# blinky_board.net
KiCad netlist of a schematic drawn in EAGLE
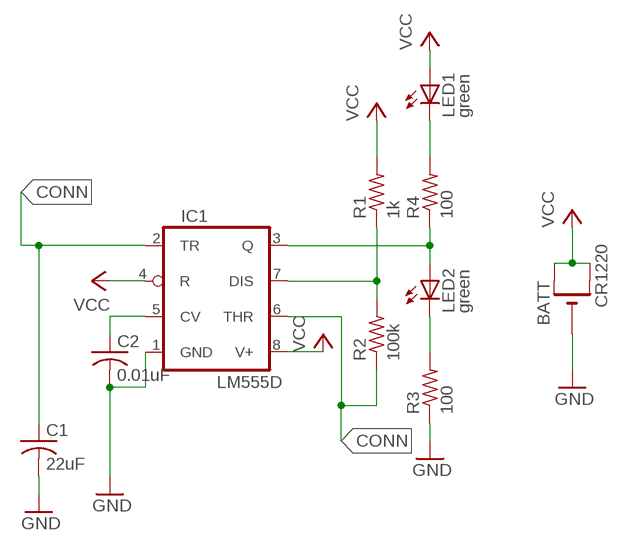
[diagram p0: schematic, sheet 1]

(export (version "E")
  (design (tool "Eeschema 10.0.6"))
  (components
    (comp (ref "BATT")
      (value "CR1220")
      (footprint "eagle-import:CR1220-SMD")
      (libsource (lib "eagle-import") (part "CR1220SMT"))
    )
    (comp (ref "C1")
      (value "22uF")
      (footprint "eagle-import:C0805")
      (fields (field (name "MF") "SAMSUNG ELECTRO-MECHANICS") (field (name "MPN") "CL21A226MPCLRNC"))
      (libsource (lib "eagle-import") (part "C-USC0805"))
    )
    (comp (ref "C2")
      (value "0.01uF")
      (footprint "eagle-import:C0805")
      (fields (field (name "MF") "KEMET") (field (name "MPN") "C0805J103K3RACAUTO"))
      (libsource (lib "eagle-import") (part "C-USC0805"))
    )
    (comp (ref "IC1")
      (value "LM555D")
      (footprint "eagle-import:SO08")
      (fields (field (name "MF") "TEXAS INSTRUMENTS") (field (name "MPN") "TLC555CDR"))
      (libsource (lib "eagle-import") (part "555DLM"))
    )
    (comp (ref "LED1")
      (value "green")
      (footprint "eagle-import:CHIPLED_0805")
      (fields (field (name "MF") "LUMEX") (field (name "MPN") "SML-LX0805GC-TR"))
      (libsource (lib "eagle-import") (part "LEDCHIPLED_0805"))
    )
    (comp (ref "LED2")
      (value "green")
      (footprint "eagle-import:CHIPLED_0805")
      (fields (field (name "MF") "LUMEX") (field (name "MPN") "SML-LX0805GC-TR"))
      (libsource (lib "eagle-import") (part "LEDCHIPLED_0805"))
    )
    (comp (ref "R1")
      (value "1k")
      (footprint "eagle-import:R0805")
      (fields (field (name "MF") "PANASONIC") (field (name "MPN") "EXBN8V102JX"))
      (libsource (lib "eagle-import") (part "R-US_R0805"))
    )
    (comp (ref "R2")
      (value "100k")
      (footprint "eagle-import:R0805")
      (fields (field (name "MF") "MULTICOMP PRO") (field (name "MPN") "MCHP05W4F1003T5E"))
      (libsource (lib "eagle-import") (part "R-US_R0805"))
    )
    (comp (ref "R3")
      (value "100")
      (footprint "eagle-import:R0805")
      (fields (field (name "MF") "VISHAY") (field (name "MPN") "CRCW0805100RJNEA"))
      (libsource (lib "eagle-import") (part "R-US_R0805"))
    )
    (comp (ref "R4")
      (value "100")
      (footprint "eagle-import:R0805")
      (fields (field (name "MF") "VISHAY") (field (name "MPN") "CRCW0805100RJNEA"))
      (libsource (lib "eagle-import") (part "R-US_R0805"))
    )
  )
  (nets
    (net (code "1") (name "CONN") (class "Default")
      (node (ref "C1") (pin "1") (pinfunction "1_1") (pintype "passive"))
      (node (ref "IC1") (pin "2") (pinfunction "TR_2") (pintype "input"))
      (node (ref "IC1") (pin "6") (pinfunction "THR_6") (pintype "input"))
      (node (ref "R2") (pin "1") (pinfunction "1_1") (pintype "passive"))
    )
    (net (code "2") (name "GND") (class "Default")
      (node (ref "BATT") (pin "-") (pinfunction "-_-") (pintype "passive"))
      (node (ref "C1") (pin "2") (pinfunction "2_2") (pintype "passive"))
      (node (ref "C2") (pin "2") (pinfunction "2_2") (pintype "passive"))
      (node (ref "IC1") (pin "1") (pinfunction "GND_1") (pintype "power_in"))
      (node (ref "R3") (pin "1") (pinfunction "1_1") (pintype "passive"))
    )
    (net (code "3") (name "Net-(IC1-CV)") (class "Default")
      (node (ref "C2") (pin "1") (pinfunction "1_1") (pintype "passive"))
      (node (ref "IC1") (pin "5") (pinfunction "CV_5") (pintype "input"))
    )
    (net (code "4") (name "Net-(IC1-DIS)") (class "Default")
      (node (ref "IC1") (pin "7") (pinfunction "DIS_7") (pintype "input"))
      (node (ref "R1") (pin "1") (pinfunction "1_1") (pintype "passive"))
      (node (ref "R2") (pin "2") (pinfunction "2_2") (pintype "passive"))
    )
    (net (code "5") (name "Net-(IC1-Q)") (class "Default")
      (node (ref "IC1") (pin "3") (pinfunction "Q_3") (pintype "output"))
      (node (ref "LED2") (pin "A") (pinfunction "A_A") (pintype "passive"))
      (node (ref "R4") (pin "1") (pinfunction "1_1") (pintype "passive"))
    )
    (net (code "6") (name "Net-(LED1-PadC)") (class "Default")
      (node (ref "LED1") (pin "C") (pinfunction "C_C") (pintype "passive"))
      (node (ref "R4") (pin "2") (pinfunction "2_2") (pintype "passive"))
    )
    (net (code "7") (name "Net-(LED2-PadC)") (class "Default")
      (node (ref "LED2") (pin "C") (pinfunction "C_C") (pintype "passive"))
      (node (ref "R3") (pin "2") (pinfunction "2_2") (pintype "passive"))
    )
    (net (code "8") (name "VCC") (class "Default")
      (node (ref "BATT") (pin "+$1") (pinfunction "+_+$1") (pintype "passive"))
      (node (ref "BATT") (pin "+$2") (pinfunction "+1_+$2") (pintype "passive"))
      (node (ref "IC1") (pin "4") (pinfunction "R_4") (pintype "input"))
      (node (ref "IC1") (pin "8") (pinfunction "V+_8") (pintype "power_in"))
      (node (ref "LED1") (pin "A") (pinfunction "A_A") (pintype "passive"))
      (node (ref "R1") (pin "2") (pinfunction "2_2") (pintype "passive"))
    )
  )
)
